# ir-kh.net
KiCad netlist of a schematic drawn in Altium Designer
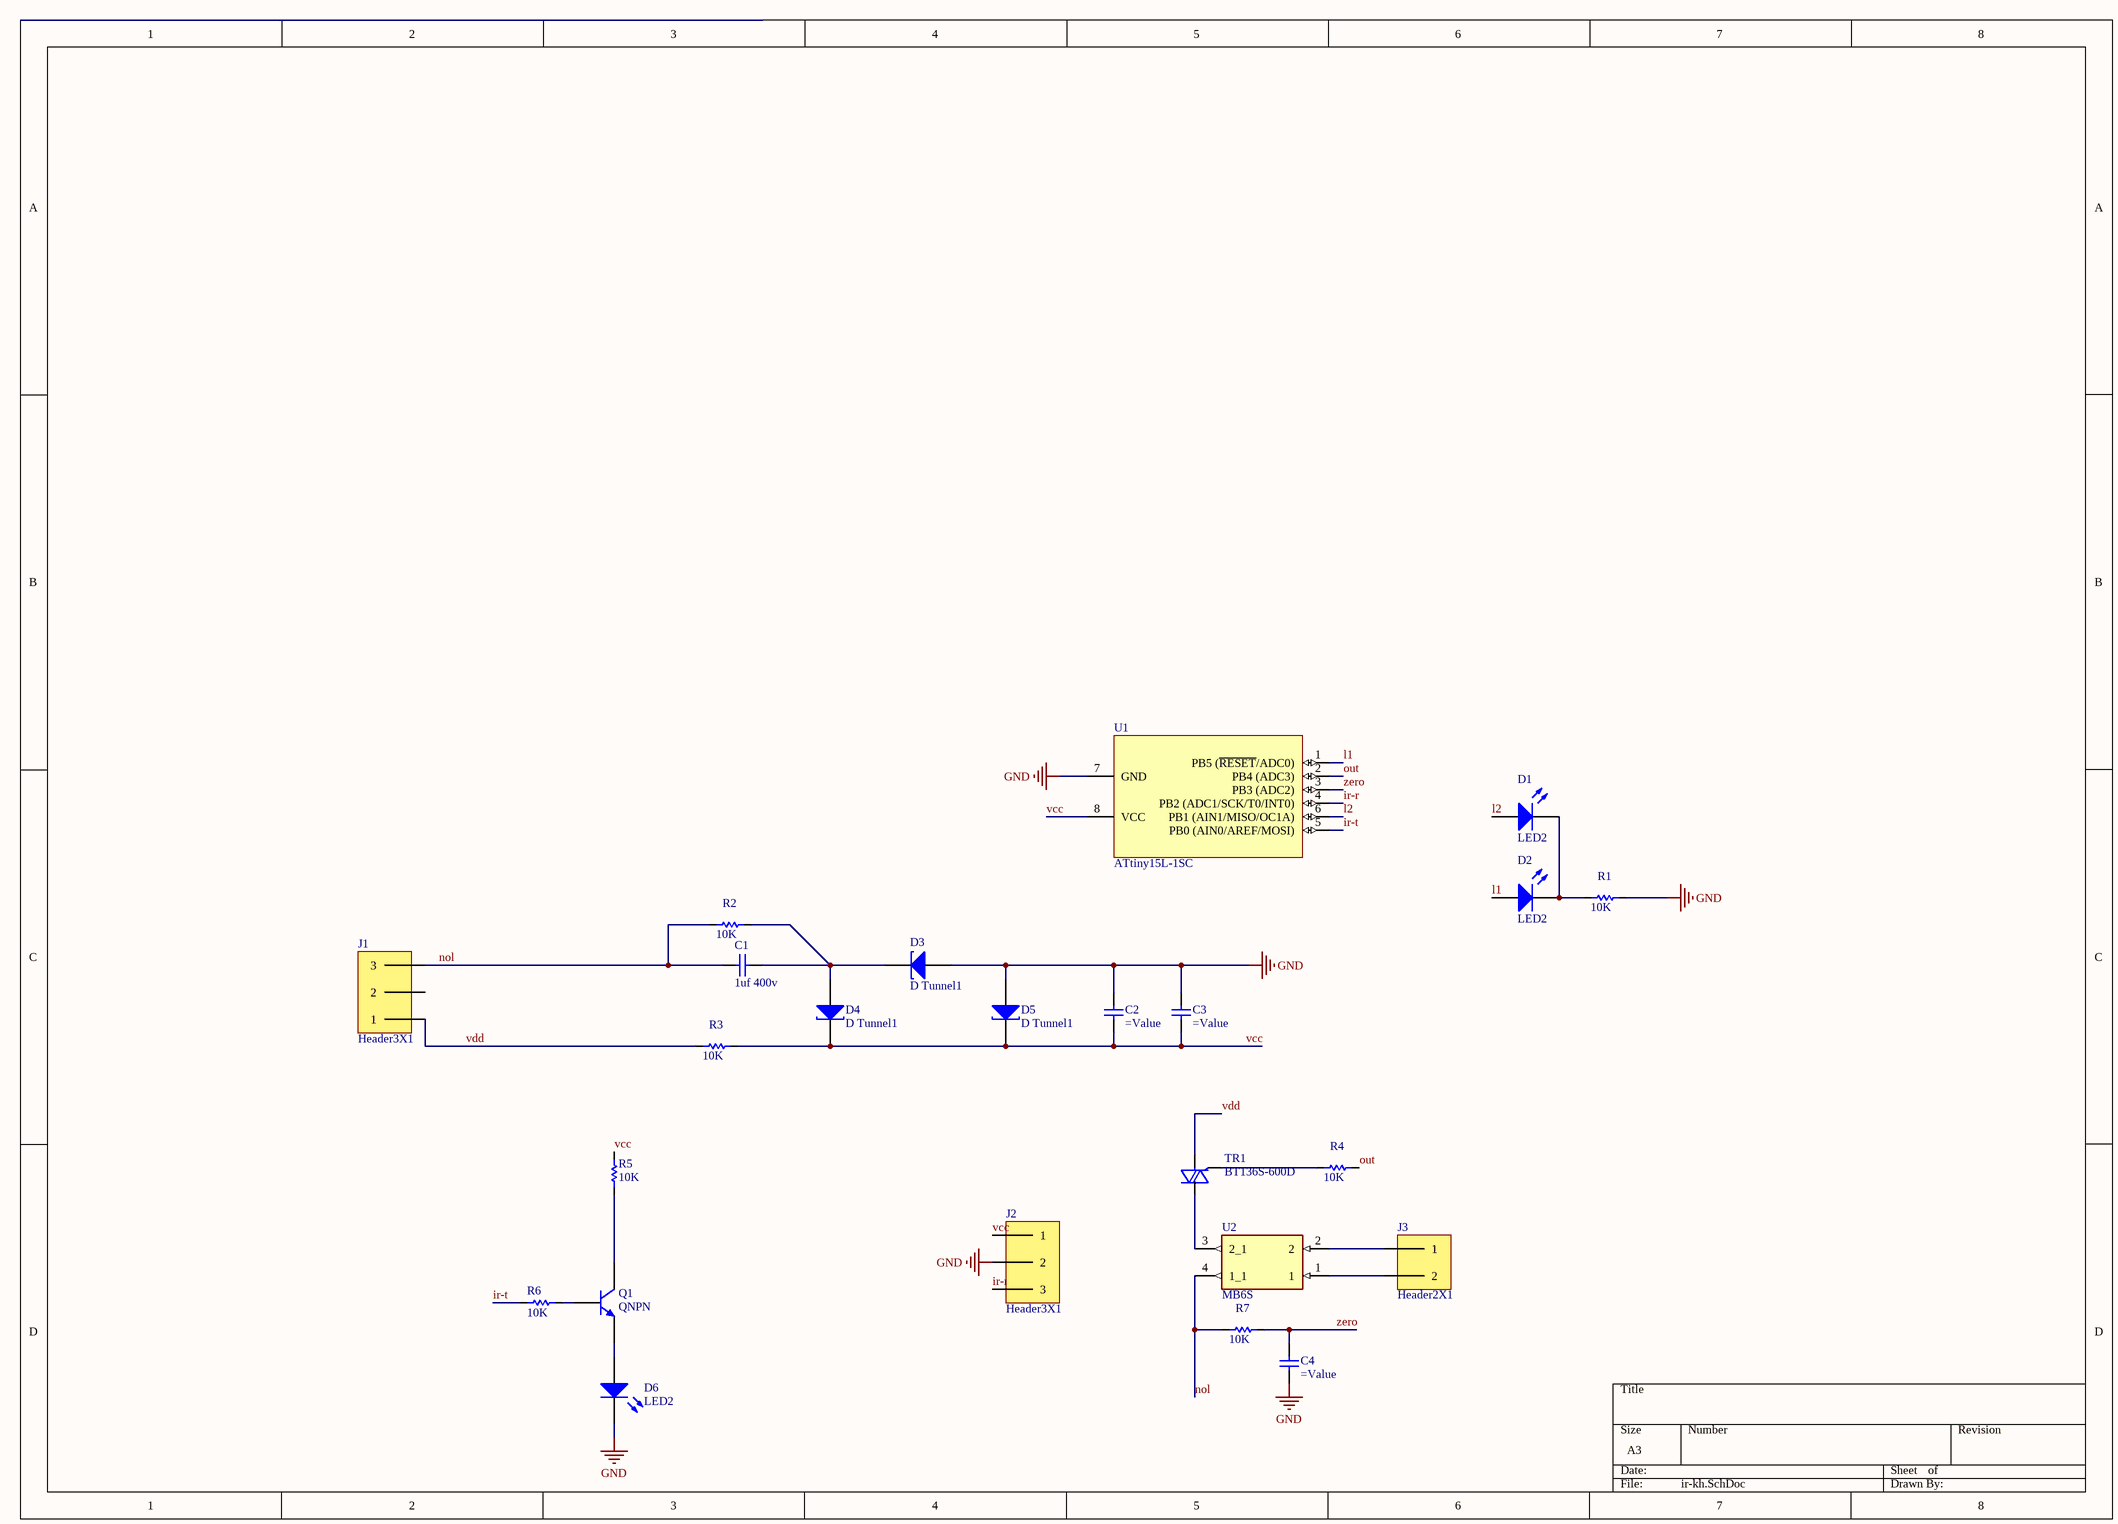
[diagram p0: ir-kh.SchDoc]

(export (version "E")
  (design (tool "Eeschema 10.0.6"))
  (components
    (comp (ref "C1")
      (value "1uf 400v")
      (footprint "1uf 400v")
      (description "Capacitor 24*9mm")
      (fields (field (name "DESIGNER") "Seyed Mohsen Ghasemain"))
      (libsource (lib "PicPars.com_usefully_Library") (part "1uf 400v"))
    )
    (comp (ref "C2")
      (value "~")
      (footprint "CAP 1206")
      (description "Capacitor")
      (libsource (lib "AltiumLib1") (part "Capacitor"))
    )
    (comp (ref "C3")
      (value "~")
      (footprint "CAP 1206")
      (description "Capacitor")
      (libsource (lib "AltiumLib1") (part "Capacitor"))
    )
    (comp (ref "C4")
      (value "~")
      (footprint "CAP 1206")
      (description "Capacitor")
      (libsource (lib "AltiumLib1") (part "Capacitor"))
    )
    (comp (ref "D1")
      (value "LED2")
      (footprint "3.2X1.6X1.1")
      (description "Typical RED, GREEN, YELLOW, AMBER GaAs LED")
      (fields (field (name "PUBLISHER") "Altium Limited"))
      (libsource (lib "Miscellaneous Devices") (part "LED2"))
    )
    (comp (ref "D2")
      (value "LED2")
      (footprint "3.2X1.6X1.1")
      (description "Typical RED, GREEN, YELLOW, AMBER GaAs LED")
      (fields (field (name "PUBLISHER") "Altium Limited"))
      (libsource (lib "Miscellaneous Devices") (part "LED2"))
    )
    (comp (ref "D3")
      (value "D Tunnel1")
      (footprint "3.2X1.6X1.1")
      (description "Tunnel Diode - RLC Model")
      (fields (field (name "PUBLISHER") "Altium Limited"))
      (libsource (lib "Miscellaneous Devices") (part "D Tunnel1"))
    )
    (comp (ref "D4")
      (value "D Tunnel1")
      (footprint "3.2X1.6X1.1")
      (description "Tunnel Diode - RLC Model")
      (fields (field (name "PUBLISHER") "Altium Limited"))
      (libsource (lib "Miscellaneous Devices") (part "D Tunnel1"))
    )
    (comp (ref "D5")
      (value "D Tunnel1")
      (footprint "3.2X1.6X1.1")
      (description "Tunnel Diode - RLC Model")
      (fields (field (name "PUBLISHER") "Altium Limited"))
      (libsource (lib "Miscellaneous Devices") (part "D Tunnel1"))
    )
    (comp (ref "D6")
      (value "LED2")
      (footprint "3.2X1.6X1.1")
      (description "Typical RED, GREEN, YELLOW, AMBER GaAs LED")
      (fields (field (name "PUBLISHER") "Altium Limited"))
      (libsource (lib "Miscellaneous Devices") (part "LED2"))
    )
    (comp (ref "J1")
      (value "Header3X1")
      (footprint "HEADER 3X1")
      (libsource (lib "AltiumLib1") (part "Header3X1"))
    )
    (comp (ref "J2") (value "Header3X1") (footprint "HEADER 3X1") (libsource (lib "") (part "Header3X1_1")))
    (comp (ref "J3")
      (value "Header2X1")
      (footprint "Header 2X1")
      (libsource (lib "AltiumLib1") (part "Header2X1"))
    )
    (comp (ref "Q1")
      (value "QNPN")
      (footprint "SOT-23B_L")
      (description "NPN Bipolar Transistor")
      (fields (field (name "PUBLISHER") "Altium Limited"))
      (libsource (lib "Miscellaneous Devices") (part "QNPN"))
    )
    (comp (ref "R1")
      (value "10K")
      (footprint "RES 1206 (3216X08L)")
      (description "Resistor")
      (fields (field (name "TOLERANCE") "5%") (field (name "POWER") "1/4 W"))
      (libsource (lib "AltiumLib1") (part "Resistor"))
    )
    (comp (ref "R2")
      (value "10K")
      (footprint "RES 1206 (3216X08L)")
      (description "Resistor")
      (fields (field (name "TOLERANCE") "5%") (field (name "POWER") "1/4 W"))
      (libsource (lib "AltiumLib1") (part "Resistor"))
    )
    (comp (ref "R3")
      (value "10K")
      (footprint "Res-(2/1)")
      (description "Resistor")
      (fields (field (name "TOLERANCE") "5%") (field (name "POWER") "1/4 W"))
      (libsource (lib "AltiumLib1") (part "Resistor"))
    )
    (comp (ref "R4")
      (value "10K")
      (footprint "RES 1206 (3216X08L)")
      (description "Resistor")
      (fields (field (name "TOLERANCE") "5%") (field (name "POWER") "1/4 W"))
      (libsource (lib "AltiumLib1") (part "Resistor"))
    )
    (comp (ref "R5")
      (value "10K")
      (footprint "RES 1206 (3216X08L)")
      (description "Resistor")
      (fields (field (name "TOLERANCE") "5%") (field (name "POWER") "1/4 W"))
      (libsource (lib "AltiumLib1") (part "Resistor"))
    )
    (comp (ref "R6")
      (value "10K")
      (footprint "RES 1206 (3216X08L)")
      (description "Resistor")
      (fields (field (name "TOLERANCE") "5%") (field (name "POWER") "1/4 W"))
      (libsource (lib "AltiumLib1") (part "Resistor"))
    )
    (comp (ref "R7")
      (value "10K")
      (footprint "RES 1206 (3216X08L)")
      (description "Resistor")
      (fields (field (name "TOLERANCE") "5%") (field (name "POWER") "1/4 W"))
      (libsource (lib "AltiumLib1") (part "Resistor"))
    )
    (comp (ref "TR1")
      (value "BT136S-600D")
      (footprint "SOT428")
      (description "TRIAC 600V 27A 3-Pin(2+Tab) DPAK")
      (fields (field (name "MF") "WeEn Semiconductor(Hong Kong)Co.,Limited"))
      (libsource (lib "BT136S-600D") (part "BT136S-600D"))
    )
    (comp (ref "U1")
      (value "ATtiny15L-1SC")
      (footprint "8S2_N")
      (description "8-Bit AVR Microcontroller with 1K Byte of Flash Memory")
      (fields (field (name "PUBLISHER") "Altium Limited"))
      (libsource (lib "Atmel Microcontroller 8-Bit AVR") (part "ATtiny15L-1SC"))
    )
    (comp (ref "U2")
      (value "MB6S")
      (footprint "SOIC245P670X270-4N")
      (description "Bridge Rectifier Single Phase Standard 600V Surface Mount 4-SOIC")
      (fields (field (name "MF") "ON Semiconductor") (field (name "DIGI-KEY_PART_NUMBER") "MB6SCT-ND"))
      (libsource (lib "MB6S") (part "MB6S"))
    )
  )
  (nets
    (net (code "1") (name "/ir-r") (class "Default")
      (node (ref "J2") (pin "3") (pinfunction "3_3") (pintype "passive"))
      (node (ref "U1") (pin "4") (pinfunction "PB2_(ADC1/SCK/T0/INT0)_4") (pintype "bidirectional"))
    )
    (net (code "2") (name "/ir-t") (class "Default")
      (node (ref "R6") (pin "1") (pinfunction "1_1") (pintype "passive"))
      (node (ref "U1") (pin "5") (pinfunction "PB0_(AIN0/AREF/MOSI)_5") (pintype "bidirectional"))
    )
    (net (code "3") (name "/l1") (class "Default")
      (node (ref "D2") (pin "1") (pinfunction "A_1") (pintype "passive"))
      (node (ref "U1") (pin "1") (pinfunction "PB5_(~{RESET}/ADC0)_1") (pintype "bidirectional"))
    )
    (net (code "4") (name "/l2") (class "Default")
      (node (ref "D1") (pin "1") (pinfunction "A_1") (pintype "passive"))
      (node (ref "U1") (pin "6") (pinfunction "PB1_(AIN1/MISO/OC1A)_6") (pintype "bidirectional"))
    )
    (net (code "5") (name "/nol") (class "Default")
      (node (ref "C1") (pin "1") (pinfunction "1_1") (pintype "passive"))
      (node (ref "J1") (pin "3") (pinfunction "3_3") (pintype "passive"))
      (node (ref "R2") (pin "1") (pinfunction "1_1") (pintype "passive"))
      (node (ref "R7") (pin "1") (pinfunction "1_1") (pintype "passive"))
      (node (ref "U2") (pin "4") (pinfunction "1_1_4") (pintype "output"))
    )
    (net (code "6") (name "/out") (class "Default")
      (node (ref "R4") (pin "2") (pinfunction "2_2") (pintype "passive"))
      (node (ref "U1") (pin "2") (pinfunction "PB4_(ADC3)_2") (pintype "bidirectional"))
    )
    (net (code "7") (name "/vcc") (class "Default")
      (node (ref "C2") (pin "1") (pinfunction "+_1") (pintype "passive"))
      (node (ref "C3") (pin "1") (pinfunction "+_1") (pintype "passive"))
      (node (ref "D4") (pin "2") (pinfunction "K_2") (pintype "passive"))
      (node (ref "D5") (pin "2") (pinfunction "K_2") (pintype "passive"))
      (node (ref "J2") (pin "1") (pinfunction "1_1") (pintype "passive"))
      (node (ref "R3") (pin "2") (pinfunction "2_2") (pintype "passive"))
      (node (ref "R5") (pin "2") (pinfunction "2_2") (pintype "passive"))
      (node (ref "U1") (pin "8") (pinfunction "VCC_8") (pintype "power_in"))
    )
    (net (code "8") (name "/vdd") (class "Default")
      (node (ref "J1") (pin "1") (pinfunction "1_1") (pintype "passive"))
      (node (ref "R3") (pin "1") (pinfunction "1_1") (pintype "passive"))
      (node (ref "TR1") (pin "1") (pinfunction "A1_1") (pintype "passive"))
    )
    (net (code "9") (name "/zero") (class "Default")
      (node (ref "C4") (pin "2") (pinfunction "-_2") (pintype "passive"))
      (node (ref "R7") (pin "2") (pinfunction "2_2") (pintype "passive"))
      (node (ref "U1") (pin "3") (pinfunction "PB3_(ADC2)_3") (pintype "bidirectional"))
    )
    (net (code "10") (name "GND") (class "Default")
      (node (ref "C2") (pin "2") (pinfunction "-_2") (pintype "passive"))
      (node (ref "C3") (pin "2") (pinfunction "-_2") (pintype "passive"))
      (node (ref "C4") (pin "1") (pinfunction "+_1") (pintype "passive"))
      (node (ref "D3") (pin "1") (pinfunction "A_1") (pintype "passive"))
      (node (ref "D5") (pin "1") (pinfunction "A_1") (pintype "passive"))
      (node (ref "D6") (pin "2") (pinfunction "K_2") (pintype "passive"))
      (node (ref "J2") (pin "2") (pinfunction "2_2") (pintype "passive"))
      (node (ref "R1") (pin "2") (pinfunction "2_2") (pintype "passive"))
      (node (ref "U1") (pin "7") (pinfunction "GND_7") (pintype "power_in"))
    )
    (net (code "11") (name "Net-(D1-K)") (class "Default")
      (node (ref "D1") (pin "2") (pinfunction "K_2") (pintype "passive"))
      (node (ref "D2") (pin "2") (pinfunction "K_2") (pintype "passive"))
      (node (ref "R1") (pin "1") (pinfunction "1_1") (pintype "passive"))
    )
    (net (code "12") (name "Net-(D3-K)") (class "Default")
      (node (ref "C1") (pin "2") (pinfunction "2_2") (pintype "passive"))
      (node (ref "D3") (pin "2") (pinfunction "K_2") (pintype "passive"))
      (node (ref "D4") (pin "1") (pinfunction "A_1") (pintype "passive"))
      (node (ref "R2") (pin "2") (pinfunction "2_2") (pintype "passive"))
    )
    (net (code "13") (name "Net-(D6-A)") (class "Default")
      (node (ref "D6") (pin "1") (pinfunction "A_1") (pintype "passive"))
      (node (ref "Q1") (pin "3") (pinfunction "E_3") (pintype "passive"))
    )
    (net (code "14") (name "Net-(J3-Pad1)") (class "Default")
      (node (ref "J3") (pin "1") (pinfunction "1_1") (pintype "passive"))
      (node (ref "U2") (pin "2") (pinfunction "2_2") (pintype "input"))
    )
    (net (code "15") (name "Net-(J3-Pad2)") (class "Default")
      (node (ref "J3") (pin "2") (pinfunction "2_2") (pintype "passive"))
      (node (ref "U2") (pin "1") (pinfunction "1_1") (pintype "input"))
    )
    (net (code "16") (name "Net-(Q1-B)") (class "Default")
      (node (ref "Q1") (pin "2") (pinfunction "B_2") (pintype "passive"))
      (node (ref "R6") (pin "2") (pinfunction "2_2") (pintype "passive"))
    )
    (net (code "17") (name "Net-(Q1-C)") (class "Default")
      (node (ref "Q1") (pin "1") (pinfunction "C_1") (pintype "passive"))
      (node (ref "R5") (pin "1") (pinfunction "1_1") (pintype "passive"))
    )
    (net (code "18") (name "Net-(TR1-A2)") (class "Default")
      (node (ref "TR1") (pin "MB") (pinfunction "A2_MB") (pintype "passive"))
      (node (ref "U2") (pin "3") (pinfunction "2_1_3") (pintype "output"))
    )
    (net (code "19") (name "Net-(TR1-G)") (class "Default")
      (node (ref "R4") (pin "1") (pinfunction "1_1") (pintype "passive"))
      (node (ref "TR1") (pin "3") (pinfunction "G_3") (pintype "passive"))
    )
    (net (code "20") (name "unconnected-(J1-Pad2)") (class "Default")
      (node (ref "J1") (pin "2") (pinfunction "2_2") (pintype "passive"))
    )
  )
)
